# semafor-c.net
KiCad netlist of a schematic drawn in EAGLE
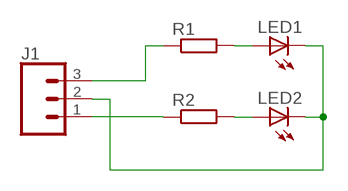
[diagram p0: schematic, sheet 1]

(export (version "E")
  (design (tool "Eeschema 10.0.6"))
  (components
    (comp (ref "J1")
      (value "CONN_031X03_NO_SILK")
      (footprint "eagle-import:1X03_NO_SILK")
      (libsource (lib "eagle-import") (part "CONN_031X03_NO_SILK"))
    )
    (comp (ref "LED1")
      (value "LED5MM")
      (footprint "eagle-import:LED5MM")
      (libsource (lib "eagle-import") (part "LED5MM"))
    )
    (comp (ref "LED2")
      (value "LED5MM")
      (footprint "eagle-import:LED5MM")
      (libsource (lib "eagle-import") (part "LED5MM"))
    )
    (comp (ref "R1")
      (value "R-EU_0207/7")
      (footprint "eagle-import:0207_7")
      (libsource (lib "eagle-import") (part "R-EU_0207/7"))
    )
    (comp (ref "R2")
      (value "R-EU_0207/7")
      (footprint "eagle-import:0207_7")
      (libsource (lib "eagle-import") (part "R-EU_0207/7"))
    )
  )
  (nets
    (net (code "1") (name "Net-(J1-Pad1)") (class "Default")
      (node (ref "J1") (pin "1") (pinfunction "1_1") (pintype "passive"))
      (node (ref "R2") (pin "1") (pinfunction "1_1") (pintype "passive"))
    )
    (net (code "2") (name "Net-(J1-Pad3)") (class "Default")
      (node (ref "J1") (pin "3") (pinfunction "3_3") (pintype "passive"))
      (node (ref "R1") (pin "1") (pinfunction "1_1") (pintype "passive"))
    )
    (net (code "3") (name "Net-(LED1-C)") (class "Default")
      (node (ref "J1") (pin "2") (pinfunction "2_2") (pintype "passive"))
      (node (ref "LED1") (pin "K") (pinfunction "C_K") (pintype "passive"))
      (node (ref "LED2") (pin "K") (pinfunction "C_K") (pintype "passive"))
    )
    (net (code "4") (name "Net-(LED1-PadA)") (class "Default")
      (node (ref "LED1") (pin "A") (pinfunction "A_A") (pintype "passive"))
      (node (ref "R1") (pin "2") (pinfunction "2_2") (pintype "passive"))
    )
    (net (code "5") (name "Net-(LED2-PadA)") (class "Default")
      (node (ref "LED2") (pin "A") (pinfunction "A_A") (pintype "passive"))
      (node (ref "R2") (pin "2") (pinfunction "2_2") (pintype "passive"))
    )
  )
)
